# Power.net
KiCad netlist of a schematic drawn in Altium Designer
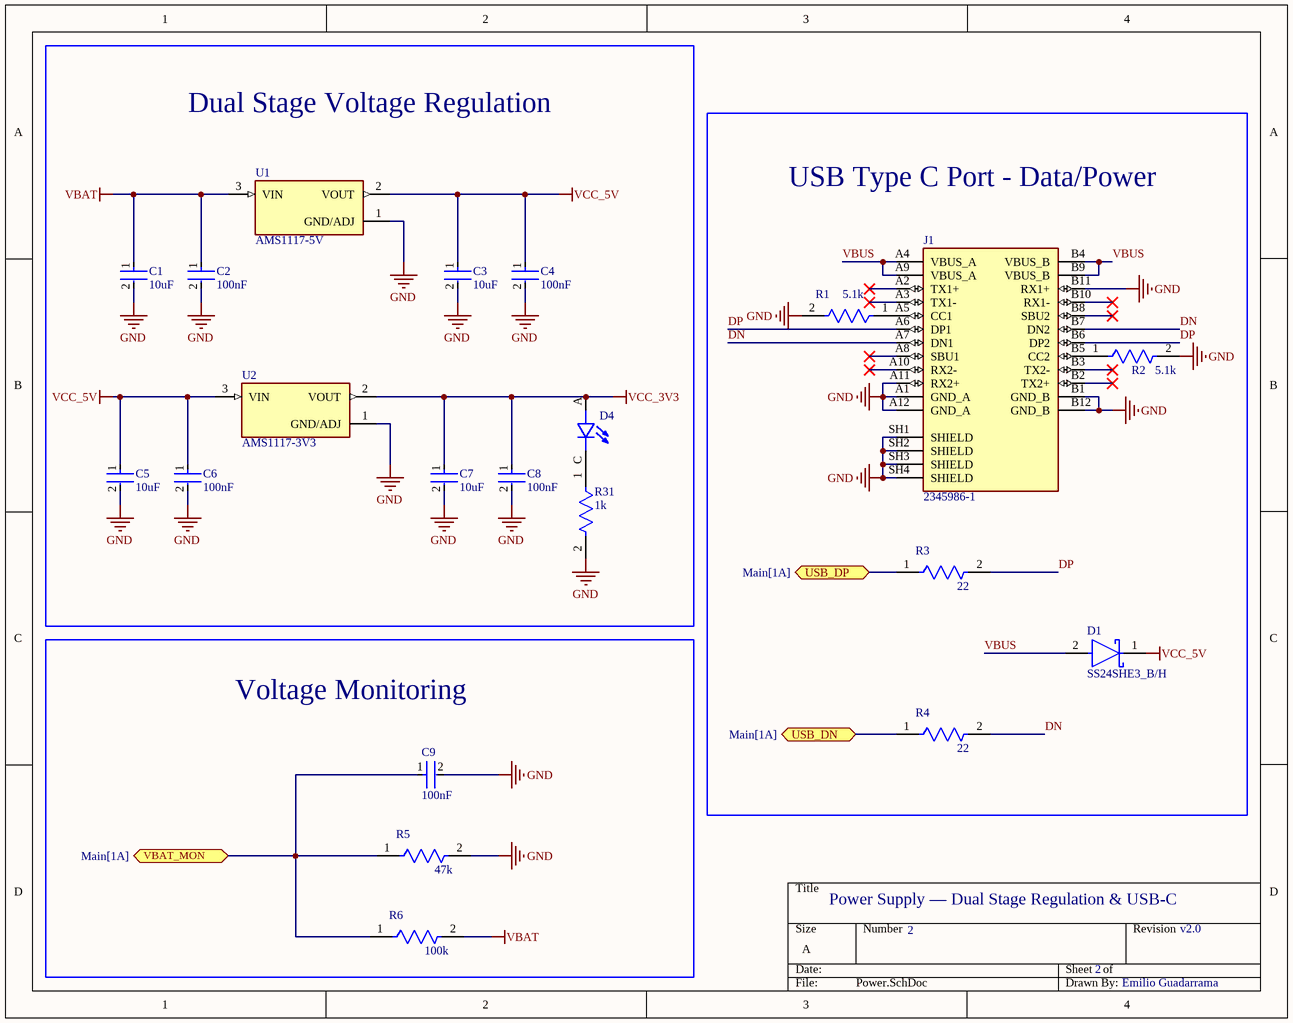
[diagram p0: Power.SchDoc]

(export (version "E")
  (design (tool "Eeschema 10.0.6"))
  (components
    (comp (ref "C1")
      (value "10uF")
      (footprint "FP-C0805C-DN-MFG")
      (description "CAP CER 0.1UF 50V X7R 0805")
      (fields
        (field (name "MANUFACTURER PART NUMBER") "C0805C104K5RACTU")
        (field (name "MANUFACTURER") "KEMET")
      )
      (libsource (lib "Altium Content Vault") (part "b4654b650e69147ec39a6b967a45e02"))
    )
    (comp (ref "C2")
      (value "100nF")
      (footprint "FP-C0805C-DN-MFG")
      (description "CAP CER 0.1UF 50V X7R 0805")
      (fields
        (field (name "MANUFACTURER PART NUMBER") "C0805C104K5RACTU")
        (field (name "MANUFACTURER") "KEMET")
      )
      (libsource (lib "Altium Content Vault") (part "b4654b650e69147ec39a6b967a45e02"))
    )
    (comp (ref "C3")
      (value "10uF")
      (footprint "FP-C0805C-DN-MFG")
      (description "CAP CER 0.1UF 50V X7R 0805")
      (fields
        (field (name "MANUFACTURER PART NUMBER") "C0805C104K5RACTU")
        (field (name "MANUFACTURER") "KEMET")
      )
      (libsource (lib "Altium Content Vault") (part "b4654b650e69147ec39a6b967a45e02"))
    )
    (comp (ref "C4")
      (value "100nF")
      (footprint "FP-C0805C-DN-MFG")
      (description "CAP CER 0.1UF 50V X7R 0805")
      (fields
        (field (name "MANUFACTURER PART NUMBER") "C0805C104K5RACTU")
        (field (name "MANUFACTURER") "KEMET")
      )
      (libsource (lib "Altium Content Vault") (part "b4654b650e69147ec39a6b967a45e02"))
    )
    (comp (ref "C5")
      (value "10uF")
      (footprint "FP-C0805C-DN-MFG")
      (description "CAP CER 0.1UF 50V X7R 0805")
      (fields
        (field (name "MANUFACTURER PART NUMBER") "C0805C104K5RACTU")
        (field (name "MANUFACTURER") "KEMET")
      )
      (libsource (lib "Altium Content Vault") (part "b4654b650e69147ec39a6b967a45e02"))
    )
    (comp (ref "C6")
      (value "100nF")
      (footprint "FP-C0805C-DN-MFG")
      (description "CAP CER 0.1UF 50V X7R 0805")
      (fields
        (field (name "MANUFACTURER PART NUMBER") "C0805C104K5RACTU")
        (field (name "MANUFACTURER") "KEMET")
      )
      (libsource (lib "Altium Content Vault") (part "b4654b650e69147ec39a6b967a45e02"))
    )
    (comp (ref "C7")
      (value "10uF")
      (footprint "FP-C0805C-DN-MFG")
      (description "CAP CER 0.1UF 50V X7R 0805")
      (fields
        (field (name "MANUFACTURER PART NUMBER") "C0805C104K5RACTU")
        (field (name "MANUFACTURER") "KEMET")
      )
      (libsource (lib "Altium Content Vault") (part "b4654b650e69147ec39a6b967a45e02"))
    )
    (comp (ref "C8")
      (value "100nF")
      (footprint "FP-C0805C-DN-MFG")
      (description "CAP CER 0.1UF 50V X7R 0805")
      (fields
        (field (name "MANUFACTURER PART NUMBER") "C0805C104K5RACTU")
        (field (name "MANUFACTURER") "KEMET")
      )
      (libsource (lib "Altium Content Vault") (part "b4654b650e69147ec39a6b967a45e02"))
    )
    (comp (ref "C9")
      (value "100nF")
      (footprint "FP-C0805C-DN-MFG")
      (description "CAP CER 0.1UF 50V X7R 0805")
      (fields
        (field (name "MANUFACTURER PART NUMBER") "C0805C104K5RACTU")
        (field (name "MANUFACTURER") "KEMET")
      )
      (libsource (lib "Altium Content Vault") (part "b4654b650e69147ec39a6b967a45e02"))
    )
    (comp (ref "D1")
      (value "SS24SHE3_B/H")
      (footprint "FP-95400-MFG")
      (description "DIODE SCHOTTKY 2A 40V DO-214AC")
      (libsource (lib "Altium Content Vault") (part "1d6ec82d83fb6aee721767c19dac4b9"))
    )
    (comp (ref "D4")
      (value "SML-LXT0805IW-TR")
      (footprint "LEDC2012X120N")
      (fields (field (name "MF") "Lumex Opto/Components"))
      (libsource (lib "LED_0805-SML-LXT0805IW-TR") (part "SML-LXT0805IW-TR"))
    )
    (comp (ref "J1")
      (value "2345986-1")
      (footprint "TE_2345986-1")
      (libsource (lib "USB_C-918-418K2023C40004") (part "2345986-1"))
    )
    (comp (ref "R1")
      (value "5.1k")
      (footprint "FP-MCT0603-IPC_A")
      (description "RES SMD 100 OHM 1% 1/8W 0603")
      (fields (field (name "TOLERANCE") "0.1%"))
      (libsource (lib "Altium Content Vault") (part "1029c3af85768c4190bb7ad29bc67b5"))
    )
    (comp (ref "R2")
      (value "5.1k")
      (footprint "FP-MCT0603-IPC_A")
      (description "RES SMD 100 OHM 1% 1/8W 0603")
      (fields (field (name "TOLERANCE") "0.1%"))
      (libsource (lib "Altium Content Vault") (part "1029c3af85768c4190bb7ad29bc67b5"))
    )
    (comp (ref "R3")
      (value "22")
      (footprint "FP-MCT0603-IPC_A")
      (description "RES SMD 100 OHM 1% 1/8W 0603")
      (fields (field (name "TOLERANCE") "0.1%"))
      (libsource (lib "Altium Content Vault") (part "1029c3af85768c4190bb7ad29bc67b5"))
    )
    (comp (ref "R4")
      (value "22")
      (footprint "FP-MCT0603-IPC_A")
      (description "RES SMD 100 OHM 1% 1/8W 0603")
      (fields (field (name "TOLERANCE") "0.1%"))
      (libsource (lib "Altium Content Vault") (part "1029c3af85768c4190bb7ad29bc67b5"))
    )
    (comp (ref "R5")
      (value "47k")
      (footprint "FP-MCT0603-IPC_A")
      (description "RES SMD 100 OHM 1% 1/8W 0603")
      (fields (field (name "TOLERANCE") "0.1%"))
      (libsource (lib "Altium Content Vault") (part "1029c3af85768c4190bb7ad29bc67b5"))
    )
    (comp (ref "R6")
      (value "100k")
      (footprint "FP-MCT0603-IPC_A")
      (description "RES SMD 100 OHM 1% 1/8W 0603")
      (fields (field (name "TOLERANCE") "0.1%"))
      (libsource (lib "Altium Content Vault") (part "1029c3af85768c4190bb7ad29bc67b5"))
    )
    (comp (ref "R31")
      (value "1k")
      (footprint "FP-MCT0603-IPC_A")
      (description "RES SMD 100 OHM 1% 1/8W 0603")
      (fields (field (name "TOLERANCE") "0.1%"))
      (libsource (lib "Altium Content Vault") (part "1029c3af85768c4190bb7ad29bc67b5"))
    )
    (comp (ref "U1")
      (value "AMS1117-5V")
      (footprint "SOT229P700X180-4N")
      (description "1A LOW DROPOUT VOLTAGE REGULATOR")
      (fields (field (name "MP") "AMS1117-5.0") (field (name "MF") "ams"))
      (libsource (lib "AMS1117-5") (part "AMS1117-5.0"))
    )
    (comp (ref "U2")
      (value "AMS1117-3V3")
      (footprint "SOT229P700X180-4N")
      (description "1A LOW DROPOUT VOLTAGE REGULATOR")
      (fields (field (name "MP") "AMS1117-5.0") (field (name "MF") "ams"))
      (libsource (lib "AMS1117-5") (part "AMS1117-5.0"))
    )
  )
  (nets
    (net (code "1") (name "/DN") (class "Default")
      (node (ref "J1") (pin "A7") (pinfunction "DN1_A7") (pintype "bidirectional"))
      (node (ref "J1") (pin "B7") (pinfunction "DN2_B7") (pintype "bidirectional"))
      (node (ref "R4") (pin "2") (pinfunction "2_2") (pintype "passive"))
    )
    (net (code "2") (name "/DP") (class "Default")
      (node (ref "J1") (pin "A6") (pinfunction "DP1_A6") (pintype "bidirectional"))
      (node (ref "J1") (pin "B6") (pinfunction "DP2_B6") (pintype "bidirectional"))
      (node (ref "R3") (pin "2") (pinfunction "2_2") (pintype "passive"))
    )
    (net (code "3") (name "/USB_DN") (class "Default")
      (node (ref "R4") (pin "1") (pinfunction "1_1") (pintype "passive"))
    )
    (net (code "4") (name "/USB_DP") (class "Default")
      (node (ref "R3") (pin "1") (pinfunction "1_1") (pintype "passive"))
    )
    (net (code "5") (name "/VBAT_MON") (class "Default")
      (node (ref "C9") (pin "1") (pinfunction "1_1") (pintype "passive"))
      (node (ref "R5") (pin "1") (pinfunction "1_1") (pintype "passive"))
      (node (ref "R6") (pin "1") (pinfunction "1_1") (pintype "passive"))
    )
    (net (code "6") (name "/VBUS") (class "Default")
      (node (ref "D1") (pin "2") (pinfunction "A_2") (pintype "passive"))
      (node (ref "J1") (pin "A4") (pinfunction "VBUS_A_A4") (pintype "power_in"))
      (node (ref "J1") (pin "A9") (pinfunction "VBUS_A_A9") (pintype "power_in"))
      (node (ref "J1") (pin "B4") (pinfunction "VBUS_B_B4") (pintype "power_in"))
      (node (ref "J1") (pin "B9") (pinfunction "VBUS_B_B9") (pintype "power_in"))
    )
    (net (code "7") (name "GND") (class "Default")
      (node (ref "C1") (pin "2") (pinfunction "2_2") (pintype "passive"))
      (node (ref "C2") (pin "2") (pinfunction "2_2") (pintype "passive"))
      (node (ref "C3") (pin "2") (pinfunction "2_2") (pintype "passive"))
      (node (ref "C4") (pin "2") (pinfunction "2_2") (pintype "passive"))
      (node (ref "C5") (pin "2") (pinfunction "2_2") (pintype "passive"))
      (node (ref "C6") (pin "2") (pinfunction "2_2") (pintype "passive"))
      (node (ref "C7") (pin "2") (pinfunction "2_2") (pintype "passive"))
      (node (ref "C8") (pin "2") (pinfunction "2_2") (pintype "passive"))
      (node (ref "C9") (pin "2") (pinfunction "2_2") (pintype "passive"))
      (node (ref "J1") (pin "A1") (pinfunction "GND_A_A1") (pintype "power_in"))
      (node (ref "J1") (pin "A11") (pinfunction "RX2+_A11") (pintype "bidirectional"))
      (node (ref "J1") (pin "A12") (pinfunction "GND_A_A12") (pintype "power_in"))
      (node (ref "J1") (pin "B1") (pinfunction "GND_B_B1") (pintype "power_in"))
      (node (ref "J1") (pin "B11") (pinfunction "RX1+_B11") (pintype "bidirectional"))
      (node (ref "J1") (pin "B12") (pinfunction "GND_B_B12") (pintype "power_in"))
      (node (ref "J1") (pin "SH1") (pinfunction "SHIELD_SH1") (pintype "passive"))
      (node (ref "J1") (pin "SH2") (pinfunction "SHIELD_SH2") (pintype "passive"))
      (node (ref "J1") (pin "SH3") (pinfunction "SHIELD_SH3") (pintype "passive"))
      (node (ref "J1") (pin "SH4") (pinfunction "SHIELD_SH4") (pintype "passive"))
      (node (ref "R1") (pin "2") (pinfunction "2_2") (pintype "passive"))
      (node (ref "R2") (pin "2") (pinfunction "2_2") (pintype "passive"))
      (node (ref "R31") (pin "2") (pinfunction "2_2") (pintype "passive"))
      (node (ref "R5") (pin "2") (pinfunction "2_2") (pintype "passive"))
      (node (ref "U1") (pin "1") (pinfunction "GND/ADJ_1") (pintype "power_in"))
      (node (ref "U2") (pin "1") (pinfunction "GND/ADJ_1") (pintype "power_in"))
    )
    (net (code "8") (name "Net-(D4-PadC)") (class "Default")
      (node (ref "D4") (pin "C") (pinfunction "C_C") (pintype "passive"))
      (node (ref "R31") (pin "1") (pinfunction "1_1") (pintype "passive"))
    )
    (net (code "9") (name "Net-(J1-CC1)") (class "Default")
      (node (ref "J1") (pin "A5") (pinfunction "CC1_A5") (pintype "bidirectional"))
      (node (ref "R1") (pin "1") (pinfunction "1_1") (pintype "passive"))
    )
    (net (code "10") (name "Net-(J1-CC2)") (class "Default")
      (node (ref "J1") (pin "B5") (pinfunction "CC2_B5") (pintype "bidirectional"))
      (node (ref "R2") (pin "1") (pinfunction "1_1") (pintype "passive"))
    )
    (net (code "11") (name "VBAT") (class "Default")
      (node (ref "C1") (pin "1") (pinfunction "1_1") (pintype "passive"))
      (node (ref "C2") (pin "1") (pinfunction "1_1") (pintype "passive"))
      (node (ref "R6") (pin "2") (pinfunction "2_2") (pintype "passive"))
      (node (ref "U1") (pin "3") (pinfunction "VIN_3") (pintype "input"))
    )
    (net (code "12") (name "VCC_3V3") (class "Default")
      (node (ref "C7") (pin "1") (pinfunction "1_1") (pintype "passive"))
      (node (ref "C8") (pin "1") (pinfunction "1_1") (pintype "passive"))
      (node (ref "D4") (pin "A") (pinfunction "A_A") (pintype "passive"))
      (node (ref "U2") (pin "2") (pinfunction "VOUT_2") (pintype "output"))
    )
    (net (code "13") (name "VCC_5V") (class "Default")
      (node (ref "C3") (pin "1") (pinfunction "1_1") (pintype "passive"))
      (node (ref "C4") (pin "1") (pinfunction "1_1") (pintype "passive"))
      (node (ref "C5") (pin "1") (pinfunction "1_1") (pintype "passive"))
      (node (ref "C6") (pin "1") (pinfunction "1_1") (pintype "passive"))
      (node (ref "D1") (pin "1") (pinfunction "C_1") (pintype "passive"))
      (node (ref "U1") (pin "2") (pinfunction "VOUT_2") (pintype "output"))
      (node (ref "U2") (pin "3") (pinfunction "VIN_3") (pintype "input"))
    )
    (net (code "14") (name "unconnected-(J1-RX1--PadB10)") (class "Default")
      (node (ref "J1") (pin "B10") (pinfunction "RX1-_B10") (pintype "bidirectional+no_connect"))
    )
    (net (code "15") (name "unconnected-(J1-RX2--PadA10)") (class "Default")
      (node (ref "J1") (pin "A10") (pinfunction "RX2-_A10") (pintype "bidirectional+no_connect"))
    )
    (net (code "16") (name "unconnected-(J1-SBU1-PadA8)") (class "Default")
      (node (ref "J1") (pin "A8") (pinfunction "SBU1_A8") (pintype "bidirectional+no_connect"))
    )
    (net (code "17") (name "unconnected-(J1-SBU2-PadB8)") (class "Default")
      (node (ref "J1") (pin "B8") (pinfunction "SBU2_B8") (pintype "bidirectional+no_connect"))
    )
    (net (code "18") (name "unconnected-(J1-TX1+-PadA2)") (class "Default")
      (node (ref "J1") (pin "A2") (pinfunction "TX1+_A2") (pintype "bidirectional+no_connect"))
    )
    (net (code "19") (name "unconnected-(J1-TX1--PadA3)") (class "Default")
      (node (ref "J1") (pin "A3") (pinfunction "TX1-_A3") (pintype "bidirectional+no_connect"))
    )
    (net (code "20") (name "unconnected-(J1-TX2+-PadB2)") (class "Default")
      (node (ref "J1") (pin "B2") (pinfunction "TX2+_B2") (pintype "bidirectional+no_connect"))
    )
    (net (code "21") (name "unconnected-(J1-TX2--PadB3)") (class "Default")
      (node (ref "J1") (pin "B3") (pinfunction "TX2-_B3") (pintype "bidirectional+no_connect"))
    )
  )
)
